# Battery_Button_Board.net
KiCad netlist of a schematic drawn in EAGLE
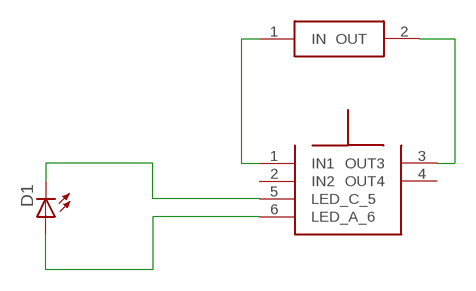
[diagram p0: schematic, sheet 1]

(export (version "E")
  (design (tool "Eeschema 10.0.6"))
  (components
    (comp (ref "D1")
      (value "LED")
      (footprint "eagle-import:XH_CONNECTOR")
      (libsource (lib "eagle-import") (part "LED"))
    )
    (comp (ref "S1")
      (value "SWITCH_CONNECTOR")
      (footprint "eagle-import:XH_CONNECTOR")
      (libsource (lib "eagle-import") (part "SWITCH_CONNECTOR"))
    )
    (comp (ref "U$1")
      (value "LED_TACT_SWITCH")
      (footprint "eagle-import:LED_TACT_SWITCH")
      (libsource (lib "eagle-import") (part "LED_TACT_SWITCH"))
    )
  )
  (nets
    (net (code "1") (name "Net-(D1-A)") (class "Default")
      (node (ref "D1") (pin "1") (pinfunction "A_1") (pintype "passive"))
      (node (ref "U$1") (pin "6") (pinfunction "LED_A_6_6") (pintype "bidirectional"))
    )
    (net (code "2") (name "Net-(D1-C)") (class "Default")
      (node (ref "D1") (pin "2") (pinfunction "C_2") (pintype "passive"))
      (node (ref "U$1") (pin "5") (pinfunction "LED_C_5_5") (pintype "bidirectional"))
    )
    (net (code "3") (name "Net-(S1-IN)") (class "Default")
      (node (ref "S1") (pin "1") (pinfunction "IN_1") (pintype "bidirectional"))
      (node (ref "U$1") (pin "1") (pinfunction "IN1_1") (pintype "bidirectional"))
    )
    (net (code "4") (name "Net-(S1-OUT)") (class "Default")
      (node (ref "S1") (pin "2") (pinfunction "OUT_2") (pintype "bidirectional"))
      (node (ref "U$1") (pin "3") (pinfunction "OUT3_3") (pintype "bidirectional"))
    )
    (net (code "5") (name "unconnected-(U$1-IN2-Pad2)") (class "Default")
      (node (ref "U$1") (pin "2") (pinfunction "IN2_2") (pintype "bidirectional"))
    )
    (net (code "6") (name "unconnected-(U$1-OUT4-Pad4)") (class "Default")
      (node (ref "U$1") (pin "4") (pinfunction "OUT4_4") (pintype "bidirectional"))
    )
  )
)
